# backplane.net
KiCad netlist of a schematic drawn in EAGLE
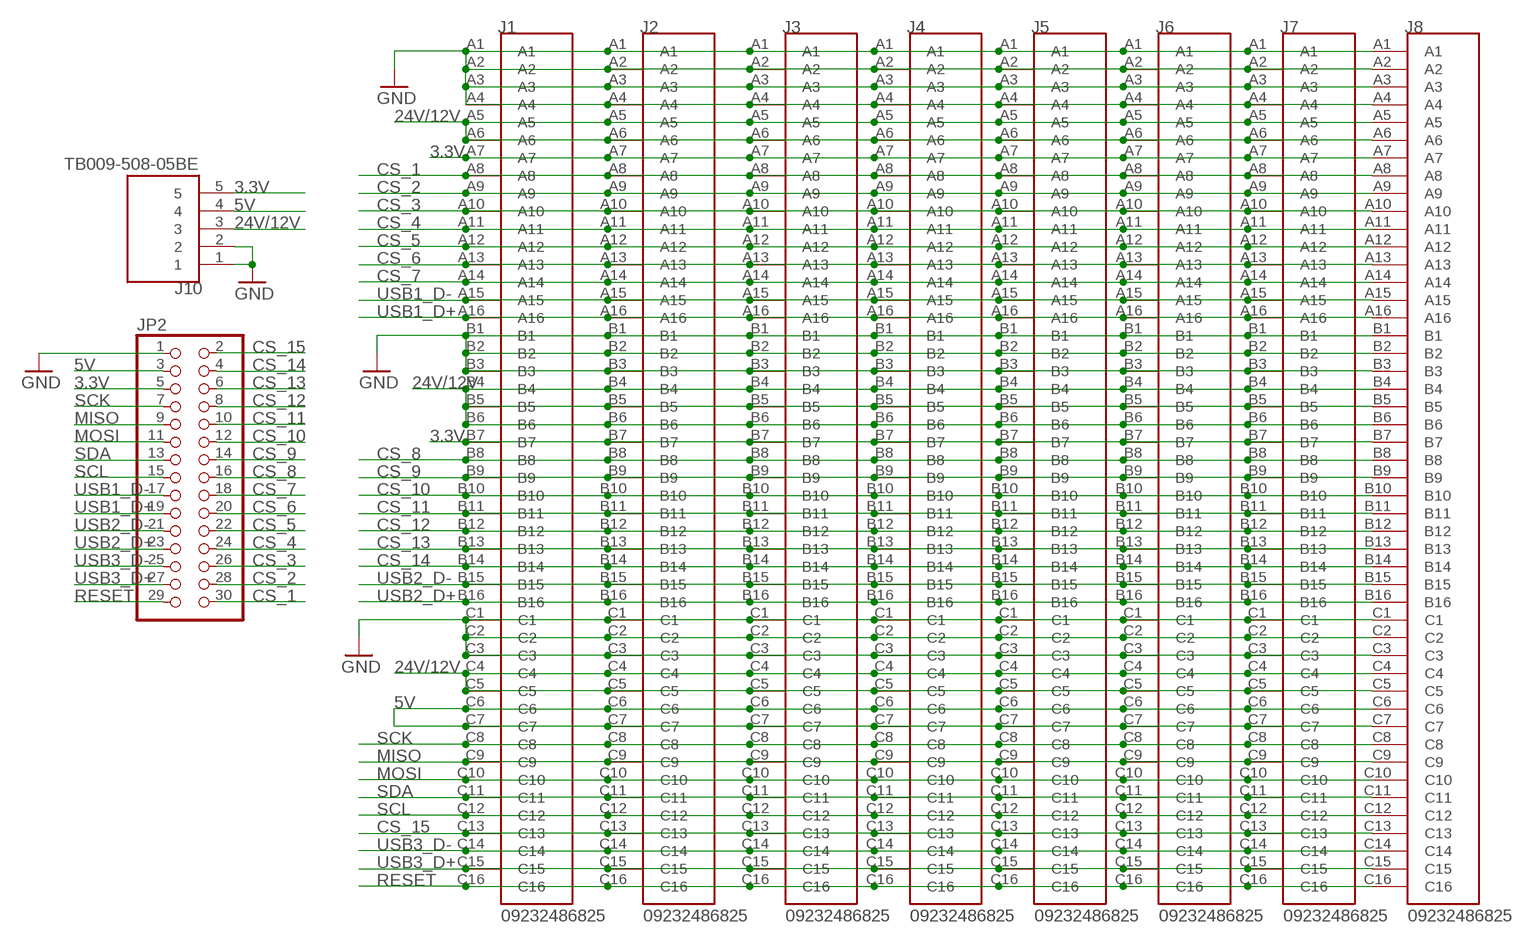
[diagram p0: schematic, sheet 1]

(export (version "E")
  (design (tool "Eeschema 10.0.6"))
  (components
    (comp (ref "J1")
      (value "09232486825")
      (footprint "eagle-import:HARTING_09232486825")
      (libsource (lib "eagle-import") (part "09232486825"))
    )
    (comp (ref "J2")
      (value "09232486825")
      (footprint "eagle-import:HARTING_09232486825")
      (libsource (lib "eagle-import") (part "09232486825"))
    )
    (comp (ref "J3")
      (value "09232486825")
      (footprint "eagle-import:HARTING_09232486825")
      (libsource (lib "eagle-import") (part "09232486825"))
    )
    (comp (ref "J4")
      (value "09232486825")
      (footprint "eagle-import:HARTING_09232486825")
      (libsource (lib "eagle-import") (part "09232486825"))
    )
    (comp (ref "J5")
      (value "09232486825")
      (footprint "eagle-import:HARTING_09232486825")
      (libsource (lib "eagle-import") (part "09232486825"))
    )
    (comp (ref "J6")
      (value "09232486825")
      (footprint "eagle-import:HARTING_09232486825")
      (libsource (lib "eagle-import") (part "09232486825"))
    )
    (comp (ref "J7")
      (value "09232486825")
      (footprint "eagle-import:HARTING_09232486825")
      (libsource (lib "eagle-import") (part "09232486825"))
    )
    (comp (ref "J8")
      (value "09232486825")
      (footprint "eagle-import:HARTING_09232486825")
      (libsource (lib "eagle-import") (part "09232486825"))
    )
    (comp (ref "J10")
      (value "TB009-508-05BE")
      (footprint "eagle-import:CUI_TB009-508-05BE")
      (libsource (lib "eagle-import") (part "TB009-508-05BE"))
    )
    (comp (ref "JP2")
      (value "PINHD-2X15")
      (footprint "eagle-import:2X15")
      (libsource (lib "eagle-import") (part "PINHD-2X15"))
    )
  )
  (nets
    (net (code "1") (name "/3.3V") (class "Default")
      (node (ref "J1") (pin "A7") (pinfunction "A7_A7") (pintype "passive"))
      (node (ref "J1") (pin "B7") (pinfunction "B7_B7") (pintype "passive"))
      (node (ref "J10") (pin "5") (pinfunction "5_5") (pintype "passive"))
      (node (ref "J2") (pin "A7") (pinfunction "A7_A7") (pintype "passive"))
      (node (ref "J2") (pin "B7") (pinfunction "B7_B7") (pintype "passive"))
      (node (ref "J3") (pin "A7") (pinfunction "A7_A7") (pintype "passive"))
      (node (ref "J3") (pin "B7") (pinfunction "B7_B7") (pintype "passive"))
      (node (ref "J4") (pin "A7") (pinfunction "A7_A7") (pintype "passive"))
      (node (ref "J4") (pin "B7") (pinfunction "B7_B7") (pintype "passive"))
      (node (ref "J5") (pin "A7") (pinfunction "A7_A7") (pintype "passive"))
      (node (ref "J5") (pin "B7") (pinfunction "B7_B7") (pintype "passive"))
      (node (ref "J6") (pin "A7") (pinfunction "A7_A7") (pintype "passive"))
      (node (ref "J6") (pin "B7") (pinfunction "B7_B7") (pintype "passive"))
      (node (ref "J7") (pin "A7") (pinfunction "A7_A7") (pintype "passive"))
      (node (ref "J7") (pin "B7") (pinfunction "B7_B7") (pintype "passive"))
      (node (ref "J8") (pin "A7") (pinfunction "A7_A7") (pintype "passive"))
      (node (ref "J8") (pin "B7") (pinfunction "B7_B7") (pintype "passive"))
      (node (ref "JP2") (pin "5") (pinfunction "5_5") (pintype "passive"))
    )
    (net (code "2") (name "/5V") (class "Default")
      (node (ref "J1") (pin "C6") (pinfunction "C6_C6") (pintype "passive"))
      (node (ref "J1") (pin "C7") (pinfunction "C7_C7") (pintype "passive"))
      (node (ref "J10") (pin "4") (pinfunction "4_4") (pintype "passive"))
      (node (ref "J2") (pin "C6") (pinfunction "C6_C6") (pintype "passive"))
      (node (ref "J2") (pin "C7") (pinfunction "C7_C7") (pintype "passive"))
      (node (ref "J3") (pin "C6") (pinfunction "C6_C6") (pintype "passive"))
      (node (ref "J3") (pin "C7") (pinfunction "C7_C7") (pintype "passive"))
      (node (ref "J4") (pin "C6") (pinfunction "C6_C6") (pintype "passive"))
      (node (ref "J4") (pin "C7") (pinfunction "C7_C7") (pintype "passive"))
      (node (ref "J5") (pin "C6") (pinfunction "C6_C6") (pintype "passive"))
      (node (ref "J5") (pin "C7") (pinfunction "C7_C7") (pintype "passive"))
      (node (ref "J6") (pin "C6") (pinfunction "C6_C6") (pintype "passive"))
      (node (ref "J6") (pin "C7") (pinfunction "C7_C7") (pintype "passive"))
      (node (ref "J7") (pin "C6") (pinfunction "C6_C6") (pintype "passive"))
      (node (ref "J7") (pin "C7") (pinfunction "C7_C7") (pintype "passive"))
      (node (ref "J8") (pin "C6") (pinfunction "C6_C6") (pintype "passive"))
      (node (ref "J8") (pin "C7") (pinfunction "C7_C7") (pintype "passive"))
      (node (ref "JP2") (pin "3") (pinfunction "3_3") (pintype "passive"))
    )
    (net (code "3") (name "/24V{slash}12V") (class "Default")
      (node (ref "J1") (pin "A5") (pinfunction "A5_A5") (pintype "passive"))
      (node (ref "J1") (pin "A6") (pinfunction "A6_A6") (pintype "passive"))
      (node (ref "J1") (pin "B4") (pinfunction "B4_B4") (pintype "passive"))
      (node (ref "J1") (pin "B5") (pinfunction "B5_B5") (pintype "passive"))
      (node (ref "J1") (pin "B6") (pinfunction "B6_B6") (pintype "passive"))
      (node (ref "J1") (pin "C4") (pinfunction "C4_C4") (pintype "passive"))
      (node (ref "J1") (pin "C5") (pinfunction "C5_C5") (pintype "passive"))
      (node (ref "J10") (pin "3") (pinfunction "3_3") (pintype "passive"))
      (node (ref "J2") (pin "A5") (pinfunction "A5_A5") (pintype "passive"))
      (node (ref "J2") (pin "A6") (pinfunction "A6_A6") (pintype "passive"))
      (node (ref "J2") (pin "B4") (pinfunction "B4_B4") (pintype "passive"))
      (node (ref "J2") (pin "B5") (pinfunction "B5_B5") (pintype "passive"))
      (node (ref "J2") (pin "B6") (pinfunction "B6_B6") (pintype "passive"))
      (node (ref "J2") (pin "C4") (pinfunction "C4_C4") (pintype "passive"))
      (node (ref "J2") (pin "C5") (pinfunction "C5_C5") (pintype "passive"))
      (node (ref "J3") (pin "A5") (pinfunction "A5_A5") (pintype "passive"))
      (node (ref "J3") (pin "A6") (pinfunction "A6_A6") (pintype "passive"))
      (node (ref "J3") (pin "B4") (pinfunction "B4_B4") (pintype "passive"))
      (node (ref "J3") (pin "B5") (pinfunction "B5_B5") (pintype "passive"))
      (node (ref "J3") (pin "B6") (pinfunction "B6_B6") (pintype "passive"))
      (node (ref "J3") (pin "C4") (pinfunction "C4_C4") (pintype "passive"))
      (node (ref "J3") (pin "C5") (pinfunction "C5_C5") (pintype "passive"))
      (node (ref "J4") (pin "A5") (pinfunction "A5_A5") (pintype "passive"))
      (node (ref "J4") (pin "A6") (pinfunction "A6_A6") (pintype "passive"))
      (node (ref "J4") (pin "B4") (pinfunction "B4_B4") (pintype "passive"))
      (node (ref "J4") (pin "B5") (pinfunction "B5_B5") (pintype "passive"))
      (node (ref "J4") (pin "B6") (pinfunction "B6_B6") (pintype "passive"))
      (node (ref "J4") (pin "C4") (pinfunction "C4_C4") (pintype "passive"))
      (node (ref "J4") (pin "C5") (pinfunction "C5_C5") (pintype "passive"))
      (node (ref "J5") (pin "A5") (pinfunction "A5_A5") (pintype "passive"))
      (node (ref "J5") (pin "A6") (pinfunction "A6_A6") (pintype "passive"))
      (node (ref "J5") (pin "B4") (pinfunction "B4_B4") (pintype "passive"))
      (node (ref "J5") (pin "B5") (pinfunction "B5_B5") (pintype "passive"))
      (node (ref "J5") (pin "B6") (pinfunction "B6_B6") (pintype "passive"))
      (node (ref "J5") (pin "C4") (pinfunction "C4_C4") (pintype "passive"))
      (node (ref "J5") (pin "C5") (pinfunction "C5_C5") (pintype "passive"))
      (node (ref "J6") (pin "A5") (pinfunction "A5_A5") (pintype "passive"))
      (node (ref "J6") (pin "A6") (pinfunction "A6_A6") (pintype "passive"))
      (node (ref "J6") (pin "B4") (pinfunction "B4_B4") (pintype "passive"))
      (node (ref "J6") (pin "B5") (pinfunction "B5_B5") (pintype "passive"))
      (node (ref "J6") (pin "B6") (pinfunction "B6_B6") (pintype "passive"))
      (node (ref "J6") (pin "C4") (pinfunction "C4_C4") (pintype "passive"))
      (node (ref "J6") (pin "C5") (pinfunction "C5_C5") (pintype "passive"))
      (node (ref "J7") (pin "A5") (pinfunction "A5_A5") (pintype "passive"))
      (node (ref "J7") (pin "A6") (pinfunction "A6_A6") (pintype "passive"))
      (node (ref "J7") (pin "B4") (pinfunction "B4_B4") (pintype "passive"))
      (node (ref "J7") (pin "B5") (pinfunction "B5_B5") (pintype "passive"))
      (node (ref "J7") (pin "B6") (pinfunction "B6_B6") (pintype "passive"))
      (node (ref "J7") (pin "C4") (pinfunction "C4_C4") (pintype "passive"))
      (node (ref "J7") (pin "C5") (pinfunction "C5_C5") (pintype "passive"))
      (node (ref "J8") (pin "A5") (pinfunction "A5_A5") (pintype "passive"))
      (node (ref "J8") (pin "A6") (pinfunction "A6_A6") (pintype "passive"))
      (node (ref "J8") (pin "B4") (pinfunction "B4_B4") (pintype "passive"))
      (node (ref "J8") (pin "B5") (pinfunction "B5_B5") (pintype "passive"))
      (node (ref "J8") (pin "B6") (pinfunction "B6_B6") (pintype "passive"))
      (node (ref "J8") (pin "C4") (pinfunction "C4_C4") (pintype "passive"))
      (node (ref "J8") (pin "C5") (pinfunction "C5_C5") (pintype "passive"))
    )
    (net (code "4") (name "/CS_1") (class "Default")
      (node (ref "J1") (pin "A8") (pinfunction "A8_A8") (pintype "passive"))
      (node (ref "J2") (pin "A8") (pinfunction "A8_A8") (pintype "passive"))
      (node (ref "J3") (pin "A8") (pinfunction "A8_A8") (pintype "passive"))
      (node (ref "J4") (pin "A8") (pinfunction "A8_A8") (pintype "passive"))
      (node (ref "J5") (pin "A8") (pinfunction "A8_A8") (pintype "passive"))
      (node (ref "J6") (pin "A8") (pinfunction "A8_A8") (pintype "passive"))
      (node (ref "J7") (pin "A8") (pinfunction "A8_A8") (pintype "passive"))
      (node (ref "J8") (pin "A8") (pinfunction "A8_A8") (pintype "passive"))
      (node (ref "JP2") (pin "30") (pinfunction "30_30") (pintype "passive"))
    )
    (net (code "5") (name "/CS_2") (class "Default")
      (node (ref "J1") (pin "A9") (pinfunction "A9_A9") (pintype "passive"))
      (node (ref "J2") (pin "A9") (pinfunction "A9_A9") (pintype "passive"))
      (node (ref "J3") (pin "A9") (pinfunction "A9_A9") (pintype "passive"))
      (node (ref "J4") (pin "A9") (pinfunction "A9_A9") (pintype "passive"))
      (node (ref "J5") (pin "A9") (pinfunction "A9_A9") (pintype "passive"))
      (node (ref "J6") (pin "A9") (pinfunction "A9_A9") (pintype "passive"))
      (node (ref "J7") (pin "A9") (pinfunction "A9_A9") (pintype "passive"))
      (node (ref "J8") (pin "A9") (pinfunction "A9_A9") (pintype "passive"))
      (node (ref "JP2") (pin "28") (pinfunction "28_28") (pintype "passive"))
    )
    (net (code "6") (name "/CS_3") (class "Default")
      (node (ref "J1") (pin "A10") (pinfunction "A10_A10") (pintype "passive"))
      (node (ref "J2") (pin "A10") (pinfunction "A10_A10") (pintype "passive"))
      (node (ref "J3") (pin "A10") (pinfunction "A10_A10") (pintype "passive"))
      (node (ref "J4") (pin "A10") (pinfunction "A10_A10") (pintype "passive"))
      (node (ref "J5") (pin "A10") (pinfunction "A10_A10") (pintype "passive"))
      (node (ref "J6") (pin "A10") (pinfunction "A10_A10") (pintype "passive"))
      (node (ref "J7") (pin "A10") (pinfunction "A10_A10") (pintype "passive"))
      (node (ref "J8") (pin "A10") (pinfunction "A10_A10") (pintype "passive"))
      (node (ref "JP2") (pin "26") (pinfunction "26_26") (pintype "passive"))
    )
    (net (code "7") (name "/CS_4") (class "Default")
      (node (ref "J1") (pin "A11") (pinfunction "A11_A11") (pintype "passive"))
      (node (ref "J2") (pin "A11") (pinfunction "A11_A11") (pintype "passive"))
      (node (ref "J3") (pin "A11") (pinfunction "A11_A11") (pintype "passive"))
      (node (ref "J4") (pin "A11") (pinfunction "A11_A11") (pintype "passive"))
      (node (ref "J5") (pin "A11") (pinfunction "A11_A11") (pintype "passive"))
      (node (ref "J6") (pin "A11") (pinfunction "A11_A11") (pintype "passive"))
      (node (ref "J7") (pin "A11") (pinfunction "A11_A11") (pintype "passive"))
      (node (ref "J8") (pin "A11") (pinfunction "A11_A11") (pintype "passive"))
      (node (ref "JP2") (pin "24") (pinfunction "24_24") (pintype "passive"))
    )
    (net (code "8") (name "/CS_5") (class "Default")
      (node (ref "J1") (pin "A12") (pinfunction "A12_A12") (pintype "passive"))
      (node (ref "J2") (pin "A12") (pinfunction "A12_A12") (pintype "passive"))
      (node (ref "J3") (pin "A12") (pinfunction "A12_A12") (pintype "passive"))
      (node (ref "J4") (pin "A12") (pinfunction "A12_A12") (pintype "passive"))
      (node (ref "J5") (pin "A12") (pinfunction "A12_A12") (pintype "passive"))
      (node (ref "J6") (pin "A12") (pinfunction "A12_A12") (pintype "passive"))
      (node (ref "J7") (pin "A12") (pinfunction "A12_A12") (pintype "passive"))
      (node (ref "J8") (pin "A12") (pinfunction "A12_A12") (pintype "passive"))
      (node (ref "JP2") (pin "22") (pinfunction "22_22") (pintype "passive"))
    )
    (net (code "9") (name "/CS_6") (class "Default")
      (node (ref "J1") (pin "A13") (pinfunction "A13_A13") (pintype "passive"))
      (node (ref "J2") (pin "A13") (pinfunction "A13_A13") (pintype "passive"))
      (node (ref "J3") (pin "A13") (pinfunction "A13_A13") (pintype "passive"))
      (node (ref "J4") (pin "A13") (pinfunction "A13_A13") (pintype "passive"))
      (node (ref "J5") (pin "A13") (pinfunction "A13_A13") (pintype "passive"))
      (node (ref "J6") (pin "A13") (pinfunction "A13_A13") (pintype "passive"))
      (node (ref "J7") (pin "A13") (pinfunction "A13_A13") (pintype "passive"))
      (node (ref "J8") (pin "A13") (pinfunction "A13_A13") (pintype "passive"))
      (node (ref "JP2") (pin "20") (pinfunction "20_20") (pintype "passive"))
    )
    (net (code "10") (name "/CS_7") (class "Default")
      (node (ref "J1") (pin "A14") (pinfunction "A14_A14") (pintype "passive"))
      (node (ref "J2") (pin "A14") (pinfunction "A14_A14") (pintype "passive"))
      (node (ref "J3") (pin "A14") (pinfunction "A14_A14") (pintype "passive"))
      (node (ref "J4") (pin "A14") (pinfunction "A14_A14") (pintype "passive"))
      (node (ref "J5") (pin "A14") (pinfunction "A14_A14") (pintype "passive"))
      (node (ref "J6") (pin "A14") (pinfunction "A14_A14") (pintype "passive"))
      (node (ref "J7") (pin "A14") (pinfunction "A14_A14") (pintype "passive"))
      (node (ref "J8") (pin "A14") (pinfunction "A14_A14") (pintype "passive"))
      (node (ref "JP2") (pin "18") (pinfunction "18_18") (pintype "passive"))
    )
    (net (code "11") (name "/CS_8") (class "Default")
      (node (ref "J1") (pin "B8") (pinfunction "B8_B8") (pintype "passive"))
      (node (ref "J2") (pin "B8") (pinfunction "B8_B8") (pintype "passive"))
      (node (ref "J3") (pin "B8") (pinfunction "B8_B8") (pintype "passive"))
      (node (ref "J4") (pin "B8") (pinfunction "B8_B8") (pintype "passive"))
      (node (ref "J5") (pin "B8") (pinfunction "B8_B8") (pintype "passive"))
      (node (ref "J6") (pin "B8") (pinfunction "B8_B8") (pintype "passive"))
      (node (ref "J7") (pin "B8") (pinfunction "B8_B8") (pintype "passive"))
      (node (ref "J8") (pin "B8") (pinfunction "B8_B8") (pintype "passive"))
      (node (ref "JP2") (pin "16") (pinfunction "16_16") (pintype "passive"))
    )
    (net (code "12") (name "/CS_9") (class "Default")
      (node (ref "J1") (pin "B9") (pinfunction "B9_B9") (pintype "passive"))
      (node (ref "J2") (pin "B9") (pinfunction "B9_B9") (pintype "passive"))
      (node (ref "J3") (pin "B9") (pinfunction "B9_B9") (pintype "passive"))
      (node (ref "J4") (pin "B9") (pinfunction "B9_B9") (pintype "passive"))
      (node (ref "J5") (pin "B9") (pinfunction "B9_B9") (pintype "passive"))
      (node (ref "J6") (pin "B9") (pinfunction "B9_B9") (pintype "passive"))
      (node (ref "J7") (pin "B9") (pinfunction "B9_B9") (pintype "passive"))
      (node (ref "J8") (pin "B9") (pinfunction "B9_B9") (pintype "passive"))
      (node (ref "JP2") (pin "14") (pinfunction "14_14") (pintype "passive"))
    )
    (net (code "13") (name "/CS_10") (class "Default")
      (node (ref "J1") (pin "B10") (pinfunction "B10_B10") (pintype "passive"))
      (node (ref "J2") (pin "B10") (pinfunction "B10_B10") (pintype "passive"))
      (node (ref "J3") (pin "B10") (pinfunction "B10_B10") (pintype "passive"))
      (node (ref "J4") (pin "B10") (pinfunction "B10_B10") (pintype "passive"))
      (node (ref "J5") (pin "B10") (pinfunction "B10_B10") (pintype "passive"))
      (node (ref "J6") (pin "B10") (pinfunction "B10_B10") (pintype "passive"))
      (node (ref "J7") (pin "B10") (pinfunction "B10_B10") (pintype "passive"))
      (node (ref "J8") (pin "B10") (pinfunction "B10_B10") (pintype "passive"))
      (node (ref "JP2") (pin "12") (pinfunction "12_12") (pintype "passive"))
    )
    (net (code "14") (name "/CS_11") (class "Default")
      (node (ref "J1") (pin "B11") (pinfunction "B11_B11") (pintype "passive"))
      (node (ref "J2") (pin "B11") (pinfunction "B11_B11") (pintype "passive"))
      (node (ref "J3") (pin "B11") (pinfunction "B11_B11") (pintype "passive"))
      (node (ref "J4") (pin "B11") (pinfunction "B11_B11") (pintype "passive"))
      (node (ref "J5") (pin "B11") (pinfunction "B11_B11") (pintype "passive"))
      (node (ref "J6") (pin "B11") (pinfunction "B11_B11") (pintype "passive"))
      (node (ref "J7") (pin "B11") (pinfunction "B11_B11") (pintype "passive"))
      (node (ref "J8") (pin "B11") (pinfunction "B11_B11") (pintype "passive"))
      (node (ref "JP2") (pin "10") (pinfunction "10_10") (pintype "passive"))
    )
    (net (code "15") (name "/CS_12") (class "Default")
      (node (ref "J1") (pin "B12") (pinfunction "B12_B12") (pintype "passive"))
      (node (ref "J2") (pin "B12") (pinfunction "B12_B12") (pintype "passive"))
      (node (ref "J3") (pin "B12") (pinfunction "B12_B12") (pintype "passive"))
      (node (ref "J4") (pin "B12") (pinfunction "B12_B12") (pintype "passive"))
      (node (ref "J5") (pin "B12") (pinfunction "B12_B12") (pintype "passive"))
      (node (ref "J6") (pin "B12") (pinfunction "B12_B12") (pintype "passive"))
      (node (ref "J7") (pin "B12") (pinfunction "B12_B12") (pintype "passive"))
      (node (ref "J8") (pin "B12") (pinfunction "B12_B12") (pintype "passive"))
      (node (ref "JP2") (pin "8") (pinfunction "8_8") (pintype "passive"))
    )
    (net (code "16") (name "/CS_13") (class "Default")
      (node (ref "J1") (pin "B13") (pinfunction "B13_B13") (pintype "passive"))
      (node (ref "J2") (pin "B13") (pinfunction "B13_B13") (pintype "passive"))
      (node (ref "J3") (pin "B13") (pinfunction "B13_B13") (pintype "passive"))
      (node (ref "J4") (pin "B13") (pinfunction "B13_B13") (pintype "passive"))
      (node (ref "J5") (pin "B13") (pinfunction "B13_B13") (pintype "passive"))
      (node (ref "J6") (pin "B13") (pinfunction "B13_B13") (pintype "passive"))
      (node (ref "J7") (pin "B13") (pinfunction "B13_B13") (pintype "passive"))
      (node (ref "J8") (pin "B13") (pinfunction "B13_B13") (pintype "passive"))
      (node (ref "JP2") (pin "6") (pinfunction "6_6") (pintype "passive"))
    )
    (net (code "17") (name "/CS_14") (class "Default")
      (node (ref "J1") (pin "B14") (pinfunction "B14_B14") (pintype "passive"))
      (node (ref "J2") (pin "B14") (pinfunction "B14_B14") (pintype "passive"))
      (node (ref "J3") (pin "B14") (pinfunction "B14_B14") (pintype "passive"))
      (node (ref "J4") (pin "B14") (pinfunction "B14_B14") (pintype "passive"))
      (node (ref "J5") (pin "B14") (pinfunction "B14_B14") (pintype "passive"))
      (node (ref "J6") (pin "B14") (pinfunction "B14_B14") (pintype "passive"))
      (node (ref "J7") (pin "B14") (pinfunction "B14_B14") (pintype "passive"))
      (node (ref "J8") (pin "B14") (pinfunction "B14_B14") (pintype "passive"))
      (node (ref "JP2") (pin "4") (pinfunction "4_4") (pintype "passive"))
    )
    (net (code "18") (name "/CS_15") (class "Default")
      (node (ref "J1") (pin "C13") (pinfunction "C13_C13") (pintype "passive"))
      (node (ref "J2") (pin "C13") (pinfunction "C13_C13") (pintype "passive"))
      (node (ref "J3") (pin "C13") (pinfunction "C13_C13") (pintype "passive"))
      (node (ref "J4") (pin "C13") (pinfunction "C13_C13") (pintype "passive"))
      (node (ref "J5") (pin "C13") (pinfunction "C13_C13") (pintype "passive"))
      (node (ref "J6") (pin "C13") (pinfunction "C13_C13") (pintype "passive"))
      (node (ref "J7") (pin "C13") (pinfunction "C13_C13") (pintype "passive"))
      (node (ref "J8") (pin "C13") (pinfunction "C13_C13") (pintype "passive"))
      (node (ref "JP2") (pin "2") (pinfunction "2_2") (pintype "passive"))
    )
    (net (code "19") (name "/MISO") (class "Default")
      (node (ref "J1") (pin "C9") (pinfunction "C9_C9") (pintype "passive"))
      (node (ref "J2") (pin "C9") (pinfunction "C9_C9") (pintype "passive"))
      (node (ref "J3") (pin "C9") (pinfunction "C9_C9") (pintype "passive"))
      (node (ref "J4") (pin "C9") (pinfunction "C9_C9") (pintype "passive"))
      (node (ref "J5") (pin "C9") (pinfunction "C9_C9") (pintype "passive"))
      (node (ref "J6") (pin "C9") (pinfunction "C9_C9") (pintype "passive"))
      (node (ref "J7") (pin "C9") (pinfunction "C9_C9") (pintype "passive"))
      (node (ref "J8") (pin "C9") (pinfunction "C9_C9") (pintype "passive"))
      (node (ref "JP2") (pin "9") (pinfunction "9_9") (pintype "passive"))
    )
    (net (code "20") (name "/MOSI") (class "Default")
      (node (ref "J1") (pin "C10") (pinfunction "C10_C10") (pintype "passive"))
      (node (ref "J2") (pin "C10") (pinfunction "C10_C10") (pintype "passive"))
      (node (ref "J3") (pin "C10") (pinfunction "C10_C10") (pintype "passive"))
      (node (ref "J4") (pin "C10") (pinfunction "C10_C10") (pintype "passive"))
      (node (ref "J5") (pin "C10") (pinfunction "C10_C10") (pintype "passive"))
      (node (ref "J6") (pin "C10") (pinfunction "C10_C10") (pintype "passive"))
      (node (ref "J7") (pin "C10") (pinfunction "C10_C10") (pintype "passive"))
      (node (ref "J8") (pin "C10") (pinfunction "C10_C10") (pintype "passive"))
      (node (ref "JP2") (pin "11") (pinfunction "11_11") (pintype "passive"))
    )
    (net (code "21") (name "/RESET") (class "Default")
      (node (ref "J1") (pin "C16") (pinfunction "C16_C16") (pintype "passive"))
      (node (ref "J2") (pin "C16") (pinfunction "C16_C16") (pintype "passive"))
      (node (ref "J3") (pin "C16") (pinfunction "C16_C16") (pintype "passive"))
      (node (ref "J4") (pin "C16") (pinfunction "C16_C16") (pintype "passive"))
      (node (ref "J5") (pin "C16") (pinfunction "C16_C16") (pintype "passive"))
      (node (ref "J6") (pin "C16") (pinfunction "C16_C16") (pintype "passive"))
      (node (ref "J7") (pin "C16") (pinfunction "C16_C16") (pintype "passive"))
      (node (ref "J8") (pin "C16") (pinfunction "C16_C16") (pintype "passive"))
      (node (ref "JP2") (pin "29") (pinfunction "29_29") (pintype "passive"))
    )
    (net (code "22") (name "/SCK") (class "Default")
      (node (ref "J1") (pin "C8") (pinfunction "C8_C8") (pintype "passive"))
      (node (ref "J2") (pin "C8") (pinfunction "C8_C8") (pintype "passive"))
      (node (ref "J3") (pin "C8") (pinfunction "C8_C8") (pintype "passive"))
      (node (ref "J4") (pin "C8") (pinfunction "C8_C8") (pintype "passive"))
      (node (ref "J5") (pin "C8") (pinfunction "C8_C8") (pintype "passive"))
      (node (ref "J6") (pin "C8") (pinfunction "C8_C8") (pintype "passive"))
      (node (ref "J7") (pin "C8") (pinfunction "C8_C8") (pintype "passive"))
      (node (ref "J8") (pin "C8") (pinfunction "C8_C8") (pintype "passive"))
      (node (ref "JP2") (pin "7") (pinfunction "7_7") (pintype "passive"))
    )
    (net (code "23") (name "/SCL") (class "Default")
      (node (ref "J1") (pin "C12") (pinfunction "C12_C12") (pintype "passive"))
      (node (ref "J2") (pin "C12") (pinfunction "C12_C12") (pintype "passive"))
      (node (ref "J3") (pin "C12") (pinfunction "C12_C12") (pintype "passive"))
      (node (ref "J4") (pin "C12") (pinfunction "C12_C12") (pintype "passive"))
      (node (ref "J5") (pin "C12") (pinfunction "C12_C12") (pintype "passive"))
      (node (ref "J6") (pin "C12") (pinfunction "C12_C12") (pintype "passive"))
      (node (ref "J7") (pin "C12") (pinfunction "C12_C12") (pintype "passive"))
      (node (ref "J8") (pin "C12") (pinfunction "C12_C12") (pintype "passive"))
      (node (ref "JP2") (pin "15") (pinfunction "15_15") (pintype "passive"))
    )
    (net (code "24") (name "/SDA") (class "Default")
      (node (ref "J1") (pin "C11") (pinfunction "C11_C11") (pintype "passive"))
      (node (ref "J2") (pin "C11") (pinfunction "C11_C11") (pintype "passive"))
      (node (ref "J3") (pin "C11") (pinfunction "C11_C11") (pintype "passive"))
      (node (ref "J4") (pin "C11") (pinfunction "C11_C11") (pintype "passive"))
      (node (ref "J5") (pin "C11") (pinfunction "C11_C11") (pintype "passive"))
      (node (ref "J6") (pin "C11") (pinfunction "C11_C11") (pintype "passive"))
      (node (ref "J7") (pin "C11") (pinfunction "C11_C11") (pintype "passive"))
      (node (ref "J8") (pin "C11") (pinfunction "C11_C11") (pintype "passive"))
      (node (ref "JP2") (pin "13") (pinfunction "13_13") (pintype "passive"))
    )
    (net (code "25") (name "/USB1_D+") (class "Default")
      (node (ref "J1") (pin "A16") (pinfunction "A16_A16") (pintype "passive"))
      (node (ref "J2") (pin "A16") (pinfunction "A16_A16") (pintype "passive"))
      (node (ref "J3") (pin "A16") (pinfunction "A16_A16") (pintype "passive"))
      (node (ref "J4") (pin "A16") (pinfunction "A16_A16") (pintype "passive"))
      (node (ref "J5") (pin "A16") (pinfunction "A16_A16") (pintype "passive"))
      (node (ref "J6") (pin "A16") (pinfunction "A16_A16") (pintype "passive"))
      (node (ref "J7") (pin "A16") (pinfunction "A16_A16") (pintype "passive"))
      (node (ref "J8") (pin "A16") (pinfunction "A16_A16") (pintype "passive"))
      (node (ref "JP2") (pin "19") (pinfunction "19_19") (pintype "passive"))
    )
    (net (code "26") (name "/USB1_D-") (class "Default")
      (node (ref "J1") (pin "A15") (pinfunction "A15_A15") (pintype "passive"))
      (node (ref "J2") (pin "A15") (pinfunction "A15_A15") (pintype "passive"))
      (node (ref "J3") (pin "A15") (pinfunction "A15_A15") (pintype "passive"))
      (node (ref "J4") (pin "A15") (pinfunction "A15_A15") (pintype "passive"))
      (node (ref "J5") (pin "A15") (pinfunction "A15_A15") (pintype "passive"))
      (node (ref "J6") (pin "A15") (pinfunction "A15_A15") (pintype "passive"))
      (node (ref "J7") (pin "A15") (pinfunction "A15_A15") (pintype "passive"))
      (node (ref "J8") (pin "A15") (pinfunction "A15_A15") (pintype "passive"))
      (node (ref "JP2") (pin "17") (pinfunction "17_17") (pintype "passive"))
    )
    (net (code "27") (name "/USB2_D+") (class "Default")
      (node (ref "J1") (pin "B16") (pinfunction "B16_B16") (pintype "passive"))
      (node (ref "J2") (pin "B16") (pinfunction "B16_B16") (pintype "passive"))
      (node (ref "J3") (pin "B16") (pinfunction "B16_B16") (pintype "passive"))
      (node (ref "J4") (pin "B16") (pinfunction "B16_B16") (pintype "passive"))
      (node (ref "J5") (pin "B16") (pinfunction "B16_B16") (pintype "passive"))
      (node (ref "J6") (pin "B16") (pinfunction "B16_B16") (pintype "passive"))
      (node (ref "J7") (pin "B16") (pinfunction "B16_B16") (pintype "passive"))
      (node (ref "J8") (pin "B16") (pinfunction "B16_B16") (pintype "passive"))
      (node (ref "JP2") (pin "23") (pinfunction "23_23") (pintype "passive"))
    )
    (net (code "28") (name "/USB2_D-") (class "Default")
      (node (ref "J1") (pin "B15") (pinfunction "B15_B15") (pintype "passive"))
      (node (ref "J2") (pin "B15") (pinfunction "B15_B15") (pintype "passive"))
      (node (ref "J3") (pin "B15") (pinfunction "B15_B15") (pintype "passive"))
      (node (ref "J4") (pin "B15") (pinfunction "B15_B15") (pintype "passive"))
      (node (ref "J5") (pin "B15") (pinfunction "B15_B15") (pintype "passive"))
      (node (ref "J6") (pin "B15") (pinfunction "B15_B15") (pintype "passive"))
      (node (ref "J7") (pin "B15") (pinfunction "B15_B15") (pintype "passive"))
      (node (ref "J8") (pin "B15") (pinfunction "B15_B15") (pintype "passive"))
      (node (ref "JP2") (pin "21") (pinfunction "21_21") (pintype "passive"))
    )
    (net (code "29") (name "/USB3_D+") (class "Default")
      (node (ref "J1") (pin "C15") (pinfunction "C15_C15") (pintype "passive"))
      (node (ref "J2") (pin "C15") (pinfunction "C15_C15") (pintype "passive"))
      (node (ref "J3") (pin "C15") (pinfunction "C15_C15") (pintype "passive"))
      (node (ref "J4") (pin "C15") (pinfunction "C15_C15") (pintype "passive"))
      (node (ref "J5") (pin "C15") (pinfunction "C15_C15") (pintype "passive"))
      (node (ref "J6") (pin "C15") (pinfunction "C15_C15") (pintype "passive"))
      (node (ref "J7") (pin "C15") (pinfunction "C15_C15") (pintype "passive"))
      (node (ref "J8") (pin "C15") (pinfunction "C15_C15") (pintype "passive"))
      (node (ref "JP2") (pin "27") (pinfunction "27_27") (pintype "passive"))
    )
    (net (code "30") (name "/USB3_D-") (class "Default")
      (node (ref "J1") (pin "C14") (pinfunction "C14_C14") (pintype "passive"))
      (node (ref "J2") (pin "C14") (pinfunction "C14_C14") (pintype "passive"))
      (node (ref "J3") (pin "C14") (pinfunction "C14_C14") (pintype "passive"))
      (node (ref "J4") (pin "C14") (pinfunction "C14_C14") (pintype "passive"))
      (node (ref "J5") (pin "C14") (pinfunction "C14_C14") (pintype "passive"))
      (node (ref "J6") (pin "C14") (pinfunction "C14_C14") (pintype "passive"))
      (node (ref "J7") (pin "C14") (pinfunction "C14_C14") (pintype "passive"))
      (node (ref "J8") (pin "C14") (pinfunction "C14_C14") (pintype "passive"))
      (node (ref "JP2") (pin "25") (pinfunction "25_25") (pintype "passive"))
    )
    (net (code "31") (name "GND") (class "Default")
      (node (ref "J1") (pin "A1") (pinfunction "A1_A1") (pintype "passive"))
      (node (ref "J1") (pin "A2") (pinfunction "A2_A2") (pintype "passive"))
      (node (ref "J1") (pin "A3") (pinfunction "A3_A3") (pintype "passive"))
      (node (ref "J1") (pin "A4") (pinfunction "A4_A4") (pintype "passive"))
      (node (ref "J1") (pin "B1") (pinfunction "B1_B1") (pintype "passive"))
      (node (ref "J1") (pin "B2") (pinfunction "B2_B2") (pintype "passive"))
      (node (ref "J1") (pin "B3") (pinfunction "B3_B3") (pintype "passive"))
      (node (ref "J1") (pin "C1") (pinfunction "C1_C1") (pintype "passive"))
      (node (ref "J1") (pin "C2") (pinfunction "C2_C2") (pintype "passive"))
      (node (ref "J1") (pin "C3") (pinfunction "C3_C3") (pintype "passive"))
      (node (ref "J10") (pin "1") (pinfunction "1_1") (pintype "passive"))
      (node (ref "J10") (pin "2") (pinfunction "2_2") (pintype "passive"))
      (node (ref "J2") (pin "A1") (pinfunction "A1_A1") (pintype "passive"))
      (node (ref "J2") (pin "A2") (pinfunction "A2_A2") (pintype "passive"))
      (node (ref "J2") (pin "A3") (pinfunction "A3_A3") (pintype "passive"))
      (node (ref "J2") (pin "A4") (pinfunction "A4_A4") (pintype "passive"))
      (node (ref "J2") (pin "B1") (pinfunction "B1_B1") (pintype "passive"))
      (node (ref "J2") (pin "B2") (pinfunction "B2_B2") (pintype "passive"))
      (node (ref "J2") (pin "B3") (pinfunction "B3_B3") (pintype "passive"))
      (node (ref "J2") (pin "C1") (pinfunction "C1_C1") (pintype "passive"))
      (node (ref "J2") (pin "C2") (pinfunction "C2_C2") (pintype "passive"))
      (node (ref "J2") (pin "C3") (pinfunction "C3_C3") (pintype "passive"))
      (node (ref "J3") (pin "A1") (pinfunction "A1_A1") (pintype "passive"))
      (node (ref "J3") (pin "A2") (pinfunction "A2_A2") (pintype "passive"))
      (node (ref "J3") (pin "A3") (pinfunction "A3_A3") (pintype "passive"))
      (node (ref "J3") (pin "A4") (pinfunction "A4_A4") (pintype "passive"))
      (node (ref "J3") (pin "B1") (pinfunction "B1_B1") (pintype "passive"))
      (node (ref "J3") (pin "B2") (pinfunction "B2_B2") (pintype "passive"))
      (node (ref "J3") (pin "B3") (pinfunction "B3_B3") (pintype "passive"))
      (node (ref "J3") (pin "C1") (pinfunction "C1_C1") (pintype "passive"))
      (node (ref "J3") (pin "C2") (pinfunction "C2_C2") (pintype "passive"))
      (node (ref "J3") (pin "C3") (pinfunction "C3_C3") (pintype "passive"))
      (node (ref "J4") (pin "A1") (pinfunction "A1_A1") (pintype "passive"))
      (node (ref "J4") (pin "A2") (pinfunction "A2_A2") (pintype "passive"))
      (node (ref "J4") (pin "A3") (pinfunction "A3_A3") (pintype "passive"))
      (node (ref "J4") (pin "A4") (pinfunction "A4_A4") (pintype "passive"))
      (node (ref "J4") (pin "B1") (pinfunction "B1_B1") (pintype "passive"))
      (node (ref "J4") (pin "B2") (pinfunction "B2_B2") (pintype "passive"))
      (node (ref "J4") (pin "B3") (pinfunction "B3_B3") (pintype "passive"))
      (node (ref "J4") (pin "C1") (pinfunction "C1_C1") (pintype "passive"))
      (node (ref "J4") (pin "C2") (pinfunction "C2_C2") (pintype "passive"))
      (node (ref "J4") (pin "C3") (pinfunction "C3_C3") (pintype "passive"))
      (node (ref "J5") (pin "A1") (pinfunction "A1_A1") (pintype "passive"))
      (node (ref "J5") (pin "A2") (pinfunction "A2_A2") (pintype "passive"))
      (node (ref "J5") (pin "A3") (pinfunction "A3_A3") (pintype "passive"))
      (node (ref "J5") (pin "A4") (pinfunction "A4_A4") (pintype "passive"))
      (node (ref "J5") (pin "B1") (pinfunction "B1_B1") (pintype "passive"))
      (node (ref "J5") (pin "B2") (pinfunction "B2_B2") (pintype "passive"))
      (node (ref "J5") (pin "B3") (pinfunction "B3_B3") (pintype "passive"))
      (node (ref "J5") (pin "C1") (pinfunction "C1_C1") (pintype "passive"))
      (node (ref "J5") (pin "C2") (pinfunction "C2_C2") (pintype "passive"))
      (node (ref "J5") (pin "C3") (pinfunction "C3_C3") (pintype "passive"))
      (node (ref "J6") (pin "A1") (pinfunction "A1_A1") (pintype "passive"))
      (node (ref "J6") (pin "A2") (pinfunction "A2_A2") (pintype "passive"))
      (node (ref "J6") (pin "A3") (pinfunction "A3_A3") (pintype "passive"))
      (node (ref "J6") (pin "A4") (pinfunction "A4_A4") (pintype "passive"))
      (node (ref "J6") (pin "B1") (pinfunction "B1_B1") (pintype "passive"))
      (node (ref "J6") (pin "B2") (pinfunction "B2_B2") (pintype "passive"))
      (node (ref "J6") (pin "B3") (pinfunction "B3_B3") (pintype "passive"))
      (node (ref "J6") (pin "C1") (pinfunction "C1_C1") (pintype "passive"))
      (node (ref "J6") (pin "C2") (pinfunction "C2_C2") (pintype "passive"))
      (node (ref "J6") (pin "C3") (pinfunction "C3_C3") (pintype "passive"))
      (node (ref "J7") (pin "A1") (pinfunction "A1_A1") (pintype "passive"))
      (node (ref "J7") (pin "A2") (pinfunction "A2_A2") (pintype "passive"))
      (node (ref "J7") (pin "A3") (pinfunction "A3_A3") (pintype "passive"))
      (node (ref "J7") (pin "A4") (pinfunction "A4_A4") (pintype "passive"))
      (node (ref "J7") (pin "B1") (pinfunction "B1_B1") (pintype "passive"))
      (node (ref "J7") (pin "B2") (pinfunction "B2_B2") (pintype "passive"))
      (node (ref "J7") (pin "B3") (pinfunction "B3_B3") (pintype "passive"))
      (node (ref "J7") (pin "C1") (pinfunction "C1_C1") (pintype "passive"))
      (node (ref "J7") (pin "C2") (pinfunction "C2_C2") (pintype "passive"))
      (node (ref "J7") (pin "C3") (pinfunction "C3_C3") (pintype "passive"))
      (node (ref "J8") (pin "A1") (pinfunction "A1_A1") (pintype "passive"))
      (node (ref "J8") (pin "A2") (pinfunction "A2_A2") (pintype "passive"))
      (node (ref "J8") (pin "A3") (pinfunction "A3_A3") (pintype "passive"))
      (node (ref "J8") (pin "A4") (pinfunction "A4_A4") (pintype "passive"))
      (node (ref "J8") (pin "B1") (pinfunction "B1_B1") (pintype "passive"))
      (node (ref "J8") (pin "B2") (pinfunction "B2_B2") (pintype "passive"))
      (node (ref "J8") (pin "B3") (pinfunction "B3_B3") (pintype "passive"))
      (node (ref "J8") (pin "C1") (pinfunction "C1_C1") (pintype "passive"))
      (node (ref "J8") (pin "C2") (pinfunction "C2_C2") (pintype "passive"))
      (node (ref "J8") (pin "C3") (pinfunction "C3_C3") (pintype "passive"))
      (node (ref "JP2") (pin "1") (pinfunction "1_1") (pintype "passive"))
    )
  )
)
